# ProDuino-PTH.net
KiCad netlist of a schematic drawn in EAGLE
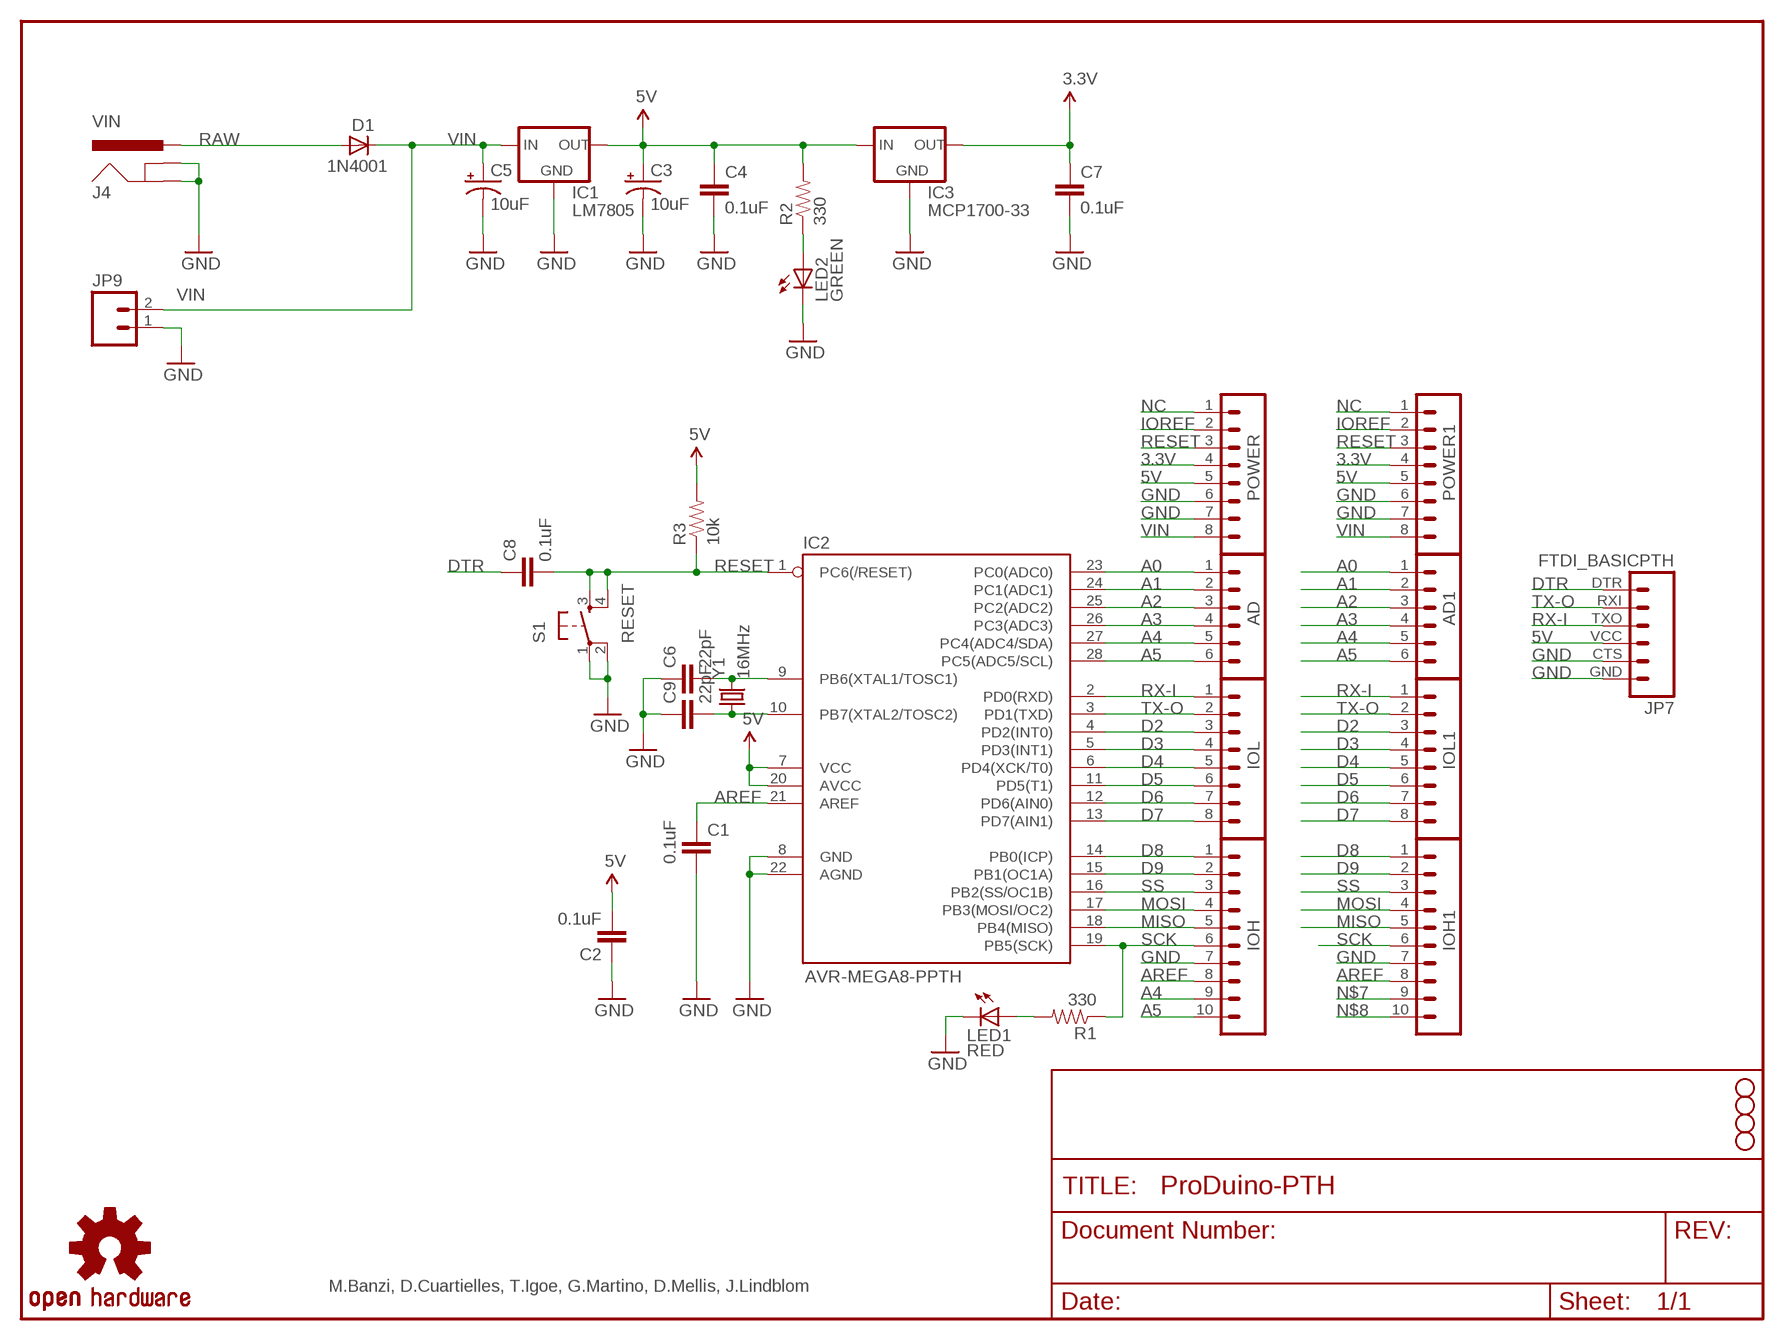
[diagram p0: schematic, sheet 1]

(export (version "E")
  (design (tool "Eeschema 10.0.6"))
  (components
    (comp (ref "AD")
      (value "M06SIP")
      (footprint "eagle-import:1X06")
      (libsource (lib "eagle-import") (part "M06SIP"))
    )
    (comp (ref "AD1")
      (value "M06SIP")
      (footprint "eagle-import:1X06")
      (libsource (lib "eagle-import") (part "M06SIP"))
    )
    (comp (ref "C1")
      (value "0.1uF")
      (footprint "eagle-import:CAP-PTH-SMALL2")
      (libsource (lib "eagle-import") (part "CAPPTH2"))
    )
    (comp (ref "C2")
      (value "0.1uF")
      (footprint "eagle-import:CAP-PTH-SMALL2")
      (libsource (lib "eagle-import") (part "CAPPTH2"))
    )
    (comp (ref "C3")
      (value "10uF")
      (footprint "eagle-import:CPOL-RADIAL-10UF-25V")
      (libsource (lib "eagle-import") (part "CAP_POLPTH2"))
    )
    (comp (ref "C4")
      (value "0.1uF")
      (footprint "eagle-import:CAP-PTH-SMALL2")
      (libsource (lib "eagle-import") (part "CAPPTH2"))
    )
    (comp (ref "C5")
      (value "10uF")
      (footprint "eagle-import:CPOL-RADIAL-10UF-25V")
      (libsource (lib "eagle-import") (part "CAP_POLPTH2"))
    )
    (comp (ref "C6")
      (value "22pF")
      (footprint "eagle-import:CAP-PTH-SMALL2")
      (libsource (lib "eagle-import") (part "CAPPTH2"))
    )
    (comp (ref "C7")
      (value "0.1uF")
      (footprint "eagle-import:CAP-PTH-SMALL2")
      (libsource (lib "eagle-import") (part "CAPPTH2"))
    )
    (comp (ref "C8")
      (value "0.1uF")
      (footprint "eagle-import:CAP-PTH-SMALL2")
      (libsource (lib "eagle-import") (part "CAPPTH2"))
    )
    (comp (ref "C9")
      (value "22pF")
      (footprint "eagle-import:CAP-PTH-SMALL2")
      (libsource (lib "eagle-import") (part "CAPPTH2"))
    )
    (comp (ref "D1")
      (value "1N4001")
      (footprint "eagle-import:DIODE-1N4001")
      (libsource (lib "eagle-import") (part "DIODEPTH"))
    )
    (comp (ref "IC1")
      (value "LM7805")
      (footprint "eagle-import:TO-220-ALT")
      (libsource (lib "eagle-import") (part "V_REG_78XX-TO-220"))
    )
    (comp (ref "IC2")
      (value "AVR-MEGA8-PPTH")
      (footprint "eagle-import:DIL28-3")
      (libsource (lib "eagle-import") (part "AVR-MEGA8-PPTH"))
    )
    (comp (ref "IC3")
      (value "MCP1700-33")
      (footprint "eagle-import:TO-92")
      (libsource (lib "eagle-import") (part "V_REG_78XXTO-92"))
    )
    (comp (ref "IOH")
      (value "M10\"")
      (footprint "eagle-import:1X10")
      (libsource (lib "eagle-import") (part "M10{dblquote}"))
    )
    (comp (ref "IOH1")
      (value "M10\"")
      (footprint "eagle-import:1X10")
      (libsource (lib "eagle-import") (part "M10{dblquote}"))
    )
    (comp (ref "IOL")
      (value "M081X08")
      (footprint "eagle-import:1X08")
      (libsource (lib "eagle-import") (part "M081X08"))
    )
    (comp (ref "IOL1")
      (value "M081X08")
      (footprint "eagle-import:1X08")
      (libsource (lib "eagle-import") (part "M081X08"))
    )
    (comp (ref "J4")
      (value "VIN")
      (footprint "eagle-import:POWER_JACK_PTH_LOCK")
      (libsource (lib "eagle-import") (part "POWER_JACKPTH_LOCK"))
    )
    (comp (ref "JP3")
      (value "STAND-OFF")
      (footprint "eagle-import:STAND-OFF")
      (libsource (lib "eagle-import") (part "STAND-OFF"))
    )
    (comp (ref "JP4")
      (value "STAND-OFF")
      (footprint "eagle-import:STAND-OFF")
      (libsource (lib "eagle-import") (part "STAND-OFF"))
    )
    (comp (ref "JP5")
      (value "STAND-OFF")
      (footprint "eagle-import:STAND-OFF")
      (libsource (lib "eagle-import") (part "STAND-OFF"))
    )
    (comp (ref "JP6")
      (value "STAND-OFF")
      (footprint "eagle-import:STAND-OFF")
      (libsource (lib "eagle-import") (part "STAND-OFF"))
    )
    (comp (ref "JP7")
      (value "FTDI_BASICPTH")
      (footprint "eagle-import:FTDI_BASIC")
      (libsource (lib "eagle-import") (part "FTDI_BASICPTH"))
    )
    (comp (ref "JP9")
      (value "M02POLAR")
      (footprint "eagle-import:MOLEX-1X2")
      (libsource (lib "eagle-import") (part "M02POLAR"))
    )
    (comp (ref "LED1")
      (value "RED")
      (footprint "eagle-import:LED5MM")
      (libsource (lib "eagle-import") (part "LED5MM"))
    )
    (comp (ref "LED2")
      (value "GREEN")
      (footprint "eagle-import:LED5MM")
      (libsource (lib "eagle-import") (part "LED5MM"))
    )
    (comp (ref "POWER")
      (value "M081X08")
      (footprint "eagle-import:1X08")
      (libsource (lib "eagle-import") (part "SparkFun-Connectors_M081X08"))
    )
    (comp (ref "POWER1")
      (value "M081X08")
      (footprint "eagle-import:1X08")
      (libsource (lib "eagle-import") (part "SparkFun-Connectors_M081X08"))
    )
    (comp (ref "R1")
      (value "330")
      (footprint "eagle-import:AXIAL-0.3")
      (libsource (lib "eagle-import") (part "RESISTORAXIAL-0.3"))
    )
    (comp (ref "R2")
      (value "330")
      (footprint "eagle-import:AXIAL-0.3")
      (libsource (lib "eagle-import") (part "RESISTORAXIAL-0.3"))
    )
    (comp (ref "R3")
      (value "10k")
      (footprint "eagle-import:AXIAL-0.3")
      (libsource (lib "eagle-import") (part "RESISTORAXIAL-0.3"))
    )
    (comp (ref "S1")
      (value "RESET")
      (footprint "eagle-import:TACTILE-PTH")
      (libsource (lib "eagle-import") (part "TAC_SWITCHPTH"))
    )
    (comp (ref "U$7")
      (value "OSHW-LOGOM")
      (footprint "eagle-import:OSHW-LOGO-M")
      (libsource (lib "eagle-import") (part "OSHW-LOGOM"))
    )
    (comp (ref "Y1")
      (value "16MHz")
      (footprint "eagle-import:HC49US")
      (libsource (lib "eagle-import") (part "CRYSTALHC49US"))
    )
  )
  (nets
    (net (code "1") (name "/A0") (class "Default")
      (node (ref "AD") (pin "1") (pinfunction "1_1") (pintype "passive"))
      (node (ref "AD1") (pin "1") (pinfunction "1_1") (pintype "passive"))
      (node (ref "IC2") (pin "23") (pinfunction "PC0(ADC0)_23") (pintype "bidirectional"))
    )
    (net (code "2") (name "/A1") (class "Default")
      (node (ref "AD") (pin "2") (pinfunction "2_2") (pintype "passive"))
      (node (ref "AD1") (pin "2") (pinfunction "2_2") (pintype "passive"))
      (node (ref "IC2") (pin "24") (pinfunction "PC1(ADC1)_24") (pintype "bidirectional"))
    )
    (net (code "3") (name "/A2") (class "Default")
      (node (ref "AD") (pin "3") (pinfunction "3_3") (pintype "passive"))
      (node (ref "AD1") (pin "3") (pinfunction "3_3") (pintype "passive"))
      (node (ref "IC2") (pin "25") (pinfunction "PC2(ADC2)_25") (pintype "bidirectional"))
    )
    (net (code "4") (name "/A3") (class "Default")
      (node (ref "AD") (pin "4") (pinfunction "4_4") (pintype "passive"))
      (node (ref "AD1") (pin "4") (pinfunction "4_4") (pintype "passive"))
      (node (ref "IC2") (pin "26") (pinfunction "PC3(ADC3)_26") (pintype "bidirectional"))
    )
    (net (code "5") (name "/A4") (class "Default")
      (node (ref "AD") (pin "5") (pinfunction "5_5") (pintype "passive"))
      (node (ref "AD1") (pin "5") (pinfunction "5_5") (pintype "passive"))
      (node (ref "IC2") (pin "27") (pinfunction "PC4(ADC4/SDA)_27") (pintype "bidirectional"))
      (node (ref "IOH") (pin "9") (pinfunction "9_9") (pintype "passive"))
    )
    (net (code "6") (name "/A5") (class "Default")
      (node (ref "AD") (pin "6") (pinfunction "6_6") (pintype "passive"))
      (node (ref "AD1") (pin "6") (pinfunction "6_6") (pintype "passive"))
      (node (ref "IC2") (pin "28") (pinfunction "PC5(ADC5/SCL)_28") (pintype "bidirectional"))
      (node (ref "IOH") (pin "10") (pinfunction "10_10") (pintype "passive"))
    )
    (net (code "7") (name "/AREF") (class "Default")
      (node (ref "C1") (pin "1") (pinfunction "1_1") (pintype "passive"))
      (node (ref "IC2") (pin "21") (pinfunction "AREF_21") (pintype "bidirectional"))
      (node (ref "IOH") (pin "8") (pinfunction "8_8") (pintype "passive"))
      (node (ref "IOH1") (pin "8") (pinfunction "8_8") (pintype "passive"))
    )
    (net (code "8") (name "/D2") (class "Default")
      (node (ref "IC2") (pin "4") (pinfunction "PD2(INT0)_4") (pintype "bidirectional"))
      (node (ref "IOL") (pin "3") (pinfunction "3_3") (pintype "passive"))
      (node (ref "IOL1") (pin "3") (pinfunction "3_3") (pintype "passive"))
    )
    (net (code "9") (name "/D3") (class "Default")
      (node (ref "IC2") (pin "5") (pinfunction "PD3(INT1)_5") (pintype "bidirectional"))
      (node (ref "IOL") (pin "4") (pinfunction "4_4") (pintype "passive"))
      (node (ref "IOL1") (pin "4") (pinfunction "4_4") (pintype "passive"))
    )
    (net (code "10") (name "/D4") (class "Default")
      (node (ref "IC2") (pin "6") (pinfunction "PD4(XCK/T0)_6") (pintype "bidirectional"))
      (node (ref "IOL") (pin "5") (pinfunction "5_5") (pintype "passive"))
      (node (ref "IOL1") (pin "5") (pinfunction "5_5") (pintype "passive"))
    )
    (net (code "11") (name "/D5") (class "Default")
      (node (ref "IC2") (pin "11") (pinfunction "PD5(T1)_11") (pintype "bidirectional"))
      (node (ref "IOL") (pin "6") (pinfunction "6_6") (pintype "passive"))
      (node (ref "IOL1") (pin "6") (pinfunction "6_6") (pintype "passive"))
    )
    (net (code "12") (name "/D6") (class "Default")
      (node (ref "IC2") (pin "12") (pinfunction "PD6(AIN0)_12") (pintype "bidirectional"))
      (node (ref "IOL") (pin "7") (pinfunction "7_7") (pintype "passive"))
      (node (ref "IOL1") (pin "7") (pinfunction "7_7") (pintype "passive"))
    )
    (net (code "13") (name "/D7") (class "Default")
      (node (ref "IC2") (pin "13") (pinfunction "PD7(AIN1)_13") (pintype "bidirectional"))
      (node (ref "IOL") (pin "8") (pinfunction "8_8") (pintype "passive"))
      (node (ref "IOL1") (pin "8") (pinfunction "8_8") (pintype "passive"))
    )
    (net (code "14") (name "/D8") (class "Default")
      (node (ref "IC2") (pin "14") (pinfunction "PB0(ICP)_14") (pintype "bidirectional"))
      (node (ref "IOH") (pin "1") (pinfunction "1_1") (pintype "passive"))
      (node (ref "IOH1") (pin "1") (pinfunction "1_1") (pintype "passive"))
    )
    (net (code "15") (name "/D9") (class "Default")
      (node (ref "IC2") (pin "15") (pinfunction "PB1(OC1A)_15") (pintype "bidirectional"))
      (node (ref "IOH") (pin "2") (pinfunction "2_2") (pintype "passive"))
      (node (ref "IOH1") (pin "2") (pinfunction "2_2") (pintype "passive"))
    )
    (net (code "16") (name "/DTR") (class "Default")
      (node (ref "C8") (pin "1") (pinfunction "1_1") (pintype "passive"))
      (node (ref "JP7") (pin "DTR") (pinfunction "1_DTR") (pintype "passive"))
    )
    (net (code "17") (name "/IOREF") (class "Default")
      (node (ref "POWER") (pin "2") (pinfunction "2_2") (pintype "passive"))
      (node (ref "POWER1") (pin "2") (pinfunction "2_2") (pintype "passive"))
    )
    (net (code "18") (name "/MISO") (class "Default")
      (node (ref "IC2") (pin "18") (pinfunction "PB4(MISO)_18") (pintype "bidirectional"))
      (node (ref "IOH") (pin "5") (pinfunction "5_5") (pintype "passive"))
      (node (ref "IOH1") (pin "5") (pinfunction "5_5") (pintype "passive"))
    )
    (net (code "19") (name "/MOSI") (class "Default")
      (node (ref "IC2") (pin "17") (pinfunction "PB3(MOSI/OC2)_17") (pintype "bidirectional"))
      (node (ref "IOH") (pin "4") (pinfunction "4_4") (pintype "passive"))
      (node (ref "IOH1") (pin "4") (pinfunction "4_4") (pintype "passive"))
    )
    (net (code "20") (name "/N$7") (class "Default")
      (node (ref "IOH1") (pin "9") (pinfunction "9_9") (pintype "passive"))
    )
    (net (code "21") (name "/N$8") (class "Default")
      (node (ref "IOH1") (pin "10") (pinfunction "10_10") (pintype "passive"))
    )
    (net (code "22") (name "/NC") (class "Default")
      (node (ref "POWER") (pin "1") (pinfunction "1_1") (pintype "passive"))
      (node (ref "POWER1") (pin "1") (pinfunction "1_1") (pintype "passive"))
    )
    (net (code "23") (name "/RAW") (class "Default")
      (node (ref "D1") (pin "A") (pinfunction "A_A") (pintype "passive"))
      (node (ref "J4") (pin "PWR") (pinfunction "PWR_PWR") (pintype "bidirectional"))
    )
    (net (code "24") (name "/RESET") (class "Default")
      (node (ref "C8") (pin "2") (pinfunction "2_2") (pintype "passive"))
      (node (ref "IC2") (pin "1") (pinfunction "PC6(/RESET)_1") (pintype "bidirectional"))
      (node (ref "POWER") (pin "3") (pinfunction "3_3") (pintype "passive"))
      (node (ref "POWER1") (pin "3") (pinfunction "3_3") (pintype "passive"))
      (node (ref "R3") (pin "P$1") (pinfunction "1_P$1") (pintype "passive"))
      (node (ref "S1") (pin "3") (pinfunction "3_3") (pintype "passive"))
      (node (ref "S1") (pin "4") (pinfunction "4_4") (pintype "passive"))
    )
    (net (code "25") (name "/RX-I") (class "Default")
      (node (ref "IC2") (pin "2") (pinfunction "PD0(RXD)_2") (pintype "bidirectional"))
      (node (ref "IOL") (pin "1") (pinfunction "1_1") (pintype "passive"))
      (node (ref "IOL1") (pin "1") (pinfunction "1_1") (pintype "passive"))
      (node (ref "JP7") (pin "TXO") (pinfunction "3_TXO") (pintype "passive"))
    )
    (net (code "26") (name "/SCK") (class "Default")
      (node (ref "IC2") (pin "19") (pinfunction "PB5(SCK)_19") (pintype "bidirectional"))
      (node (ref "IOH") (pin "6") (pinfunction "6_6") (pintype "passive"))
      (node (ref "IOH1") (pin "6") (pinfunction "6_6") (pintype "passive"))
      (node (ref "R1") (pin "P$1") (pinfunction "1_P$1") (pintype "passive"))
    )
    (net (code "27") (name "/SS") (class "Default")
      (node (ref "IC2") (pin "16") (pinfunction "PB2(SS/OC1B)_16") (pintype "bidirectional"))
      (node (ref "IOH") (pin "3") (pinfunction "3_3") (pintype "passive"))
      (node (ref "IOH1") (pin "3") (pinfunction "3_3") (pintype "passive"))
    )
    (net (code "28") (name "/TX-O") (class "Default")
      (node (ref "IC2") (pin "3") (pinfunction "PD1(TXD)_3") (pintype "bidirectional"))
      (node (ref "IOL") (pin "2") (pinfunction "2_2") (pintype "passive"))
      (node (ref "IOL1") (pin "2") (pinfunction "2_2") (pintype "passive"))
      (node (ref "JP7") (pin "RXI") (pinfunction "2_RXI") (pintype "passive"))
    )
    (net (code "29") (name "/VIN") (class "Default")
      (node (ref "C5") (pin "1") (pinfunction "+_1") (pintype "passive"))
      (node (ref "D1") (pin "C") (pinfunction "C_C") (pintype "passive"))
      (node (ref "IC1") (pin "IN") (pinfunction "IN_IN") (pintype "input"))
      (node (ref "JP9") (pin "2") (pinfunction "2_2") (pintype "passive"))
      (node (ref "POWER") (pin "8") (pinfunction "8_8") (pintype "passive"))
      (node (ref "POWER1") (pin "8") (pinfunction "8_8") (pintype "passive"))
    )
    (net (code "30") (name "3.3V") (class "Default")
      (node (ref "C7") (pin "1") (pinfunction "1_1") (pintype "passive"))
      (node (ref "IC3") (pin "3") (pinfunction "OUT_3") (pintype "output"))
      (node (ref "POWER") (pin "4") (pinfunction "4_4") (pintype "passive"))
      (node (ref "POWER1") (pin "4") (pinfunction "4_4") (pintype "passive"))
    )
    (net (code "31") (name "5V") (class "Default")
      (node (ref "C2") (pin "2") (pinfunction "2_2") (pintype "passive"))
      (node (ref "C3") (pin "1") (pinfunction "+_1") (pintype "passive"))
      (node (ref "C4") (pin "1") (pinfunction "1_1") (pintype "passive"))
      (node (ref "IC1") (pin "OUT") (pinfunction "OUT_OUT") (pintype "output"))
      (node (ref "IC2") (pin "20") (pinfunction "AVCC_20") (pintype "bidirectional"))
      (node (ref "IC2") (pin "7") (pinfunction "VCC_7") (pintype "bidirectional"))
      (node (ref "IC3") (pin "2") (pinfunction "IN_2") (pintype "input"))
      (node (ref "JP7") (pin "VCC") (pinfunction "4_VCC") (pintype "passive"))
      (node (ref "POWER") (pin "5") (pinfunction "5_5") (pintype "passive"))
      (node (ref "POWER1") (pin "5") (pinfunction "5_5") (pintype "passive"))
      (node (ref "R2") (pin "P$2") (pinfunction "2_P$2") (pintype "passive"))
      (node (ref "R3") (pin "P$2") (pinfunction "2_P$2") (pintype "passive"))
    )
    (net (code "32") (name "GND") (class "Default")
      (node (ref "C1") (pin "2") (pinfunction "2_2") (pintype "passive"))
      (node (ref "C2") (pin "1") (pinfunction "1_1") (pintype "passive"))
      (node (ref "C3") (pin "2") (pinfunction "-_2") (pintype "passive"))
      (node (ref "C4") (pin "2") (pinfunction "2_2") (pintype "passive"))
      (node (ref "C5") (pin "2") (pinfunction "-_2") (pintype "passive"))
      (node (ref "C6") (pin "1") (pinfunction "1_1") (pintype "passive"))
      (node (ref "C7") (pin "2") (pinfunction "2_2") (pintype "passive"))
      (node (ref "C9") (pin "1") (pinfunction "1_1") (pintype "passive"))
      (node (ref "IC1") (pin "GND") (pinfunction "GND_GND") (pintype "input"))
      (node (ref "IC2") (pin "22") (pinfunction "AGND_22") (pintype "bidirectional"))
      (node (ref "IC2") (pin "8") (pinfunction "GND_8") (pintype "bidirectional"))
      (node (ref "IC3") (pin "1") (pinfunction "GND_1") (pintype "input"))
      (node (ref "IOH") (pin "7") (pinfunction "7_7") (pintype "passive"))
      (node (ref "IOH1") (pin "7") (pinfunction "7_7") (pintype "passive"))
      (node (ref "J4") (pin "GND") (pinfunction "GND_GND") (pintype "bidirectional"))
      (node (ref "J4") (pin "GNDBREAK") (pinfunction "GNDBREAK_GNDBREAK") (pintype "bidirectional"))
      (node (ref "JP7") (pin "CTS") (pinfunction "5_CTS") (pintype "passive"))
      (node (ref "JP7") (pin "GND") (pinfunction "6_GND") (pintype "passive"))
      (node (ref "JP9") (pin "1") (pinfunction "1_1") (pintype "passive"))
      (node (ref "LED1") (pin "K") (pinfunction "C_K") (pintype "passive"))
      (node (ref "LED2") (pin "K") (pinfunction "C_K") (pintype "passive"))
      (node (ref "POWER") (pin "6") (pinfunction "6_6") (pintype "passive"))
      (node (ref "POWER") (pin "7") (pinfunction "7_7") (pintype "passive"))
      (node (ref "POWER1") (pin "6") (pinfunction "6_6") (pintype "passive"))
      (node (ref "POWER1") (pin "7") (pinfunction "7_7") (pintype "passive"))
      (node (ref "S1") (pin "1") (pinfunction "1_1") (pintype "passive"))
      (node (ref "S1") (pin "2") (pinfunction "2_2") (pintype "passive"))
    )
    (net (code "33") (name "Net-(IC2-PB6(XTAL1{slash}TOSC1))") (class "Default")
      (node (ref "C6") (pin "2") (pinfunction "2_2") (pintype "passive"))
      (node (ref "IC2") (pin "9") (pinfunction "PB6(XTAL1/TOSC1)_9") (pintype "bidirectional"))
      (node (ref "Y1") (pin "2") (pinfunction "2_2") (pintype "passive"))
    )
    (net (code "34") (name "Net-(IC2-PB7(XTAL2{slash}TOSC2))") (class "Default")
      (node (ref "C9") (pin "2") (pinfunction "2_2") (pintype "passive"))
      (node (ref "IC2") (pin "10") (pinfunction "PB7(XTAL2/TOSC2)_10") (pintype "bidirectional"))
      (node (ref "Y1") (pin "1") (pinfunction "1_1") (pintype "passive"))
    )
    (net (code "35") (name "Net-(R1-2)") (class "Default")
      (node (ref "LED1") (pin "A") (pinfunction "A_A") (pintype "passive"))
      (node (ref "R1") (pin "P$2") (pinfunction "2_P$2") (pintype "passive"))
    )
    (net (code "36") (name "Net-(R2-1)") (class "Default")
      (node (ref "LED2") (pin "A") (pinfunction "A_A") (pintype "passive"))
      (node (ref "R2") (pin "P$1") (pinfunction "1_P$1") (pintype "passive"))
    )
  )
)
